# XOR.net
KiCad netlist of a schematic drawn in EAGLE
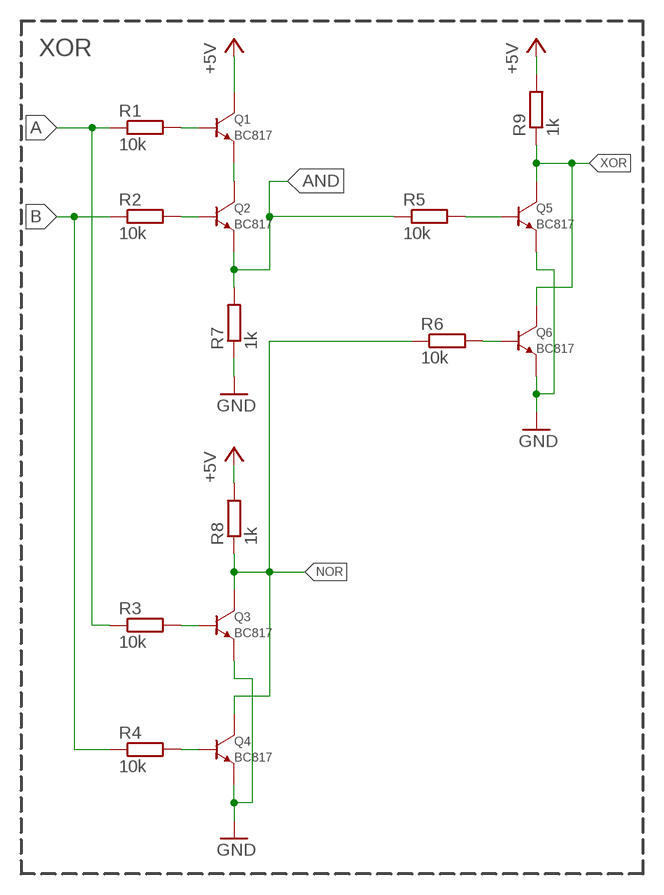
[diagram p0: schematic, sheet 1]

(export (version "E")
  (design (tool "Eeschema 10.0.6"))
  (components
    (comp (ref "Q1")
      (value "BC817")
      (footprint "eagle-import:SOT23")
      (libsource (lib "eagle-import") (part "TRANSISTOR-NPN-GENERIC-SOT23-BECDEFAULT"))
    )
    (comp (ref "Q2")
      (value "BC817")
      (footprint "eagle-import:SOT23")
      (libsource (lib "eagle-import") (part "TRANSISTOR-NPN-GENERIC-SOT23-BECDEFAULT"))
    )
    (comp (ref "Q3")
      (value "BC817")
      (footprint "eagle-import:SOT23")
      (libsource (lib "eagle-import") (part "TRANSISTOR-NPN-GENERIC-SOT23-BECDEFAULT"))
    )
    (comp (ref "Q4")
      (value "BC817")
      (footprint "eagle-import:SOT23")
      (libsource (lib "eagle-import") (part "TRANSISTOR-NPN-GENERIC-SOT23-BECDEFAULT"))
    )
    (comp (ref "Q5")
      (value "BC817")
      (footprint "eagle-import:SOT23")
      (libsource (lib "eagle-import") (part "TRANSISTOR-NPN-GENERIC-SOT23-BECDEFAULT"))
    )
    (comp (ref "Q6")
      (value "BC817")
      (footprint "eagle-import:SOT23")
      (libsource (lib "eagle-import") (part "TRANSISTOR-NPN-GENERIC-SOT23-BECDEFAULT"))
    )
    (comp (ref "R1")
      (value "10k")
      (footprint "eagle-import:R0805")
      (libsource (lib "eagle-import") (part "R-EU_R0805"))
    )
    (comp (ref "R2")
      (value "10k")
      (footprint "eagle-import:R0805")
      (libsource (lib "eagle-import") (part "R-EU_R0805"))
    )
    (comp (ref "R3")
      (value "10k")
      (footprint "eagle-import:R0805")
      (libsource (lib "eagle-import") (part "R-EU_R0805"))
    )
    (comp (ref "R4")
      (value "10k")
      (footprint "eagle-import:R0805")
      (libsource (lib "eagle-import") (part "R-EU_R0805"))
    )
    (comp (ref "R5")
      (value "10k")
      (footprint "eagle-import:R0805")
      (libsource (lib "eagle-import") (part "R-EU_R0805"))
    )
    (comp (ref "R6")
      (value "10k")
      (footprint "eagle-import:R0805")
      (libsource (lib "eagle-import") (part "R-EU_R0805"))
    )
    (comp (ref "R7")
      (value "1k")
      (footprint "eagle-import:R0805")
      (libsource (lib "eagle-import") (part "R-EU_R0805"))
    )
    (comp (ref "R8")
      (value "1k")
      (footprint "eagle-import:R0805")
      (libsource (lib "eagle-import") (part "R-EU_R0805"))
    )
    (comp (ref "R9")
      (value "1k")
      (footprint "eagle-import:R0805")
      (libsource (lib "eagle-import") (part "R-EU_R0805"))
    )
  )
  (nets
    (net (code "1") (name "+5V") (class "Default")
      (node (ref "Q1") (pin "P$3") (pinfunction "COLLECTOR_P$3") (pintype "bidirectional"))
      (node (ref "R8") (pin "2") (pinfunction "2_2") (pintype "passive"))
      (node (ref "R9") (pin "2") (pinfunction "2_2") (pintype "passive"))
    )
    (net (code "2") (name "A") (class "Default")
      (node (ref "R1") (pin "1") (pinfunction "1_1") (pintype "passive"))
      (node (ref "R3") (pin "1") (pinfunction "1_1") (pintype "passive"))
    )
    (net (code "3") (name "AND") (class "Default")
      (node (ref "Q2") (pin "P$2") (pinfunction "EMITTER_P$2") (pintype "bidirectional"))
      (node (ref "R5") (pin "1") (pinfunction "1_1") (pintype "passive"))
      (node (ref "R7") (pin "2") (pinfunction "2_2") (pintype "passive"))
    )
    (net (code "4") (name "B") (class "Default")
      (node (ref "R2") (pin "1") (pinfunction "1_1") (pintype "passive"))
      (node (ref "R4") (pin "1") (pinfunction "1_1") (pintype "passive"))
    )
    (net (code "5") (name "GND") (class "Default")
      (node (ref "Q3") (pin "P$2") (pinfunction "EMITTER_P$2") (pintype "bidirectional"))
      (node (ref "Q4") (pin "P$2") (pinfunction "EMITTER_P$2") (pintype "bidirectional"))
      (node (ref "Q5") (pin "P$2") (pinfunction "EMITTER_P$2") (pintype "bidirectional"))
      (node (ref "Q6") (pin "P$2") (pinfunction "EMITTER_P$2") (pintype "bidirectional"))
      (node (ref "R7") (pin "1") (pinfunction "1_1") (pintype "passive"))
    )
    (net (code "6") (name "NOR") (class "Default")
      (node (ref "Q3") (pin "P$3") (pinfunction "COLLECTOR_P$3") (pintype "bidirectional"))
      (node (ref "Q4") (pin "P$3") (pinfunction "COLLECTOR_P$3") (pintype "bidirectional"))
      (node (ref "R6") (pin "1") (pinfunction "1_1") (pintype "passive"))
      (node (ref "R8") (pin "1") (pinfunction "1_1") (pintype "passive"))
    )
    (net (code "7") (name "Net-(Q1-BASE)") (class "Default")
      (node (ref "Q1") (pin "P$1") (pinfunction "BASE_P$1") (pintype "bidirectional"))
      (node (ref "R1") (pin "2") (pinfunction "2_2") (pintype "passive"))
    )
    (net (code "8") (name "Net-(Q1-EMITTER)") (class "Default")
      (node (ref "Q1") (pin "P$2") (pinfunction "EMITTER_P$2") (pintype "bidirectional"))
      (node (ref "Q2") (pin "P$3") (pinfunction "COLLECTOR_P$3") (pintype "bidirectional"))
    )
    (net (code "9") (name "Net-(Q2-BASE)") (class "Default")
      (node (ref "Q2") (pin "P$1") (pinfunction "BASE_P$1") (pintype "bidirectional"))
      (node (ref "R2") (pin "2") (pinfunction "2_2") (pintype "passive"))
    )
    (net (code "10") (name "Net-(Q3-BASE)") (class "Default")
      (node (ref "Q3") (pin "P$1") (pinfunction "BASE_P$1") (pintype "bidirectional"))
      (node (ref "R3") (pin "2") (pinfunction "2_2") (pintype "passive"))
    )
    (net (code "11") (name "Net-(Q4-BASE)") (class "Default")
      (node (ref "Q4") (pin "P$1") (pinfunction "BASE_P$1") (pintype "bidirectional"))
      (node (ref "R4") (pin "2") (pinfunction "2_2") (pintype "passive"))
    )
    (net (code "12") (name "Net-(Q5-BASE)") (class "Default")
      (node (ref "Q5") (pin "P$1") (pinfunction "BASE_P$1") (pintype "bidirectional"))
      (node (ref "R5") (pin "2") (pinfunction "2_2") (pintype "passive"))
    )
    (net (code "13") (name "Net-(Q6-BASE)") (class "Default")
      (node (ref "Q6") (pin "P$1") (pinfunction "BASE_P$1") (pintype "bidirectional"))
      (node (ref "R6") (pin "2") (pinfunction "2_2") (pintype "passive"))
    )
    (net (code "14") (name "XOR") (class "Default")
      (node (ref "Q5") (pin "P$3") (pinfunction "COLLECTOR_P$3") (pintype "bidirectional"))
      (node (ref "Q6") (pin "P$3") (pinfunction "COLLECTOR_P$3") (pintype "bidirectional"))
      (node (ref "R9") (pin "1") (pinfunction "1_1") (pintype "passive"))
    )
  )
)
